# ProPrj_acoustic_imager_2026-03-04.net
KiCad netlist of a schematic drawn in EasyEDA Pro
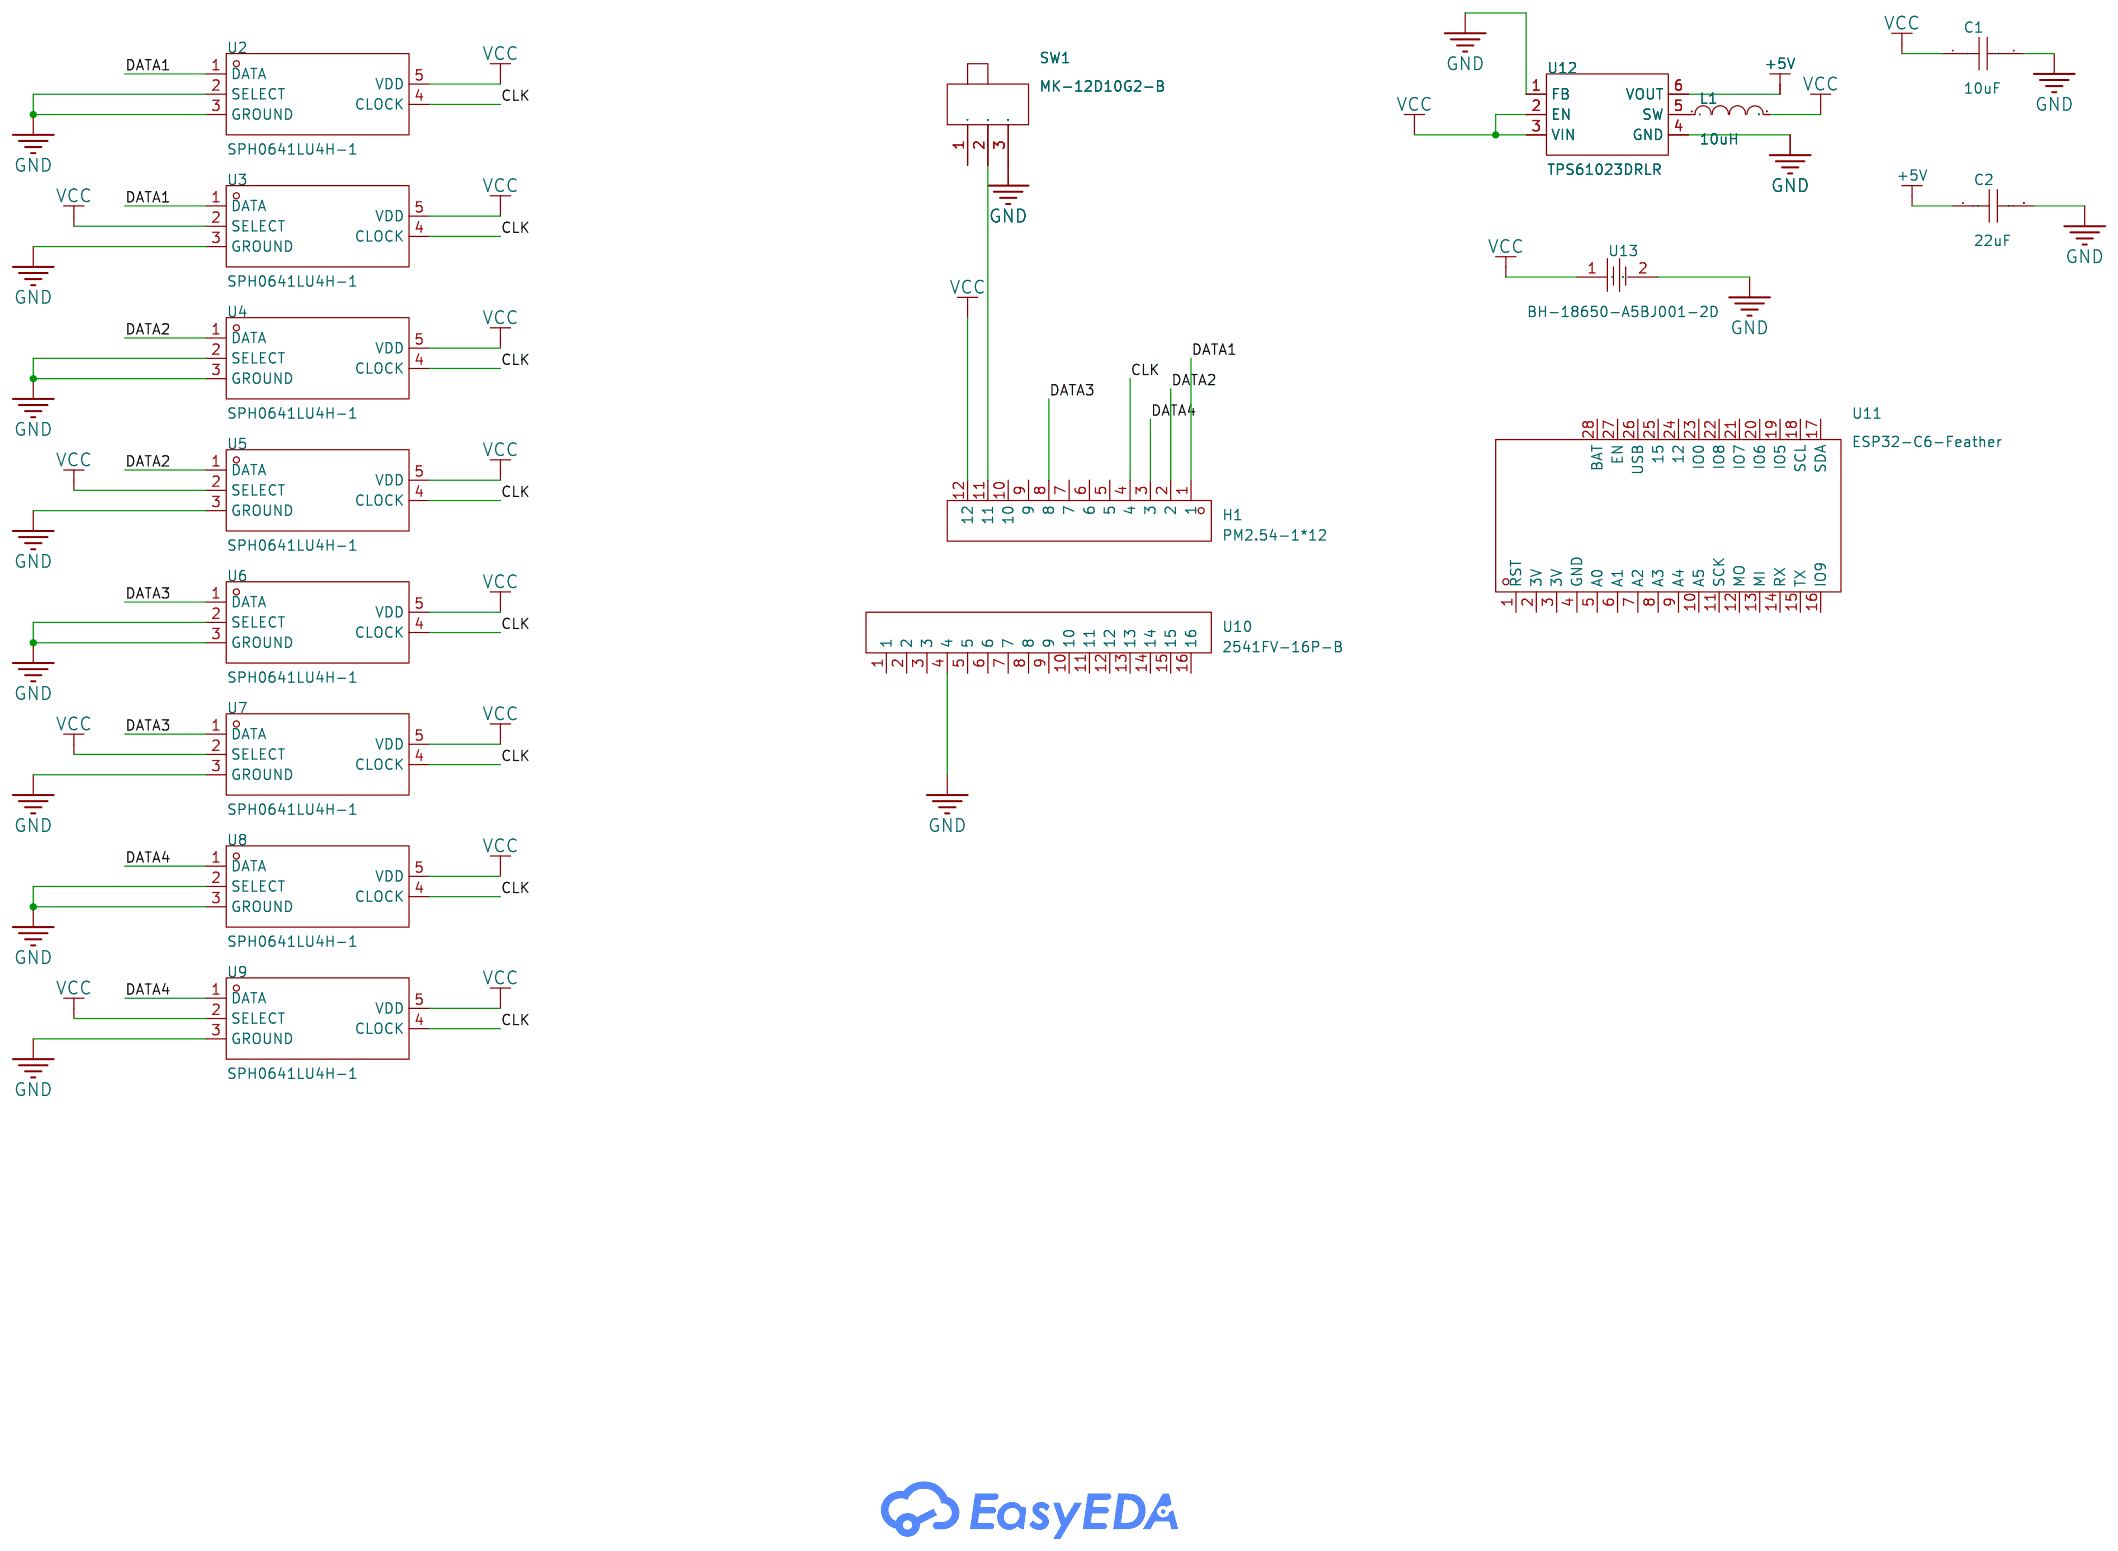
[diagram p0: schematic sheet]

(export (version "E")
  (design (tool "Eeschema 10.0.6"))
  (components
    (comp (ref "C1")
      (value "10uF")
      (footprint "easyedapro:C0805")
      (description "Capacitance:10uF Tolerance:±10% Tolerance:±10% Voltage Rating:50V Temperature Coefficient:X5R")
      (fields
        (field (name "Manufacturer Part") "GRM21BR61H106KE43L")
        (field (name "Manufacturer") "muRata(村田)")
      )
      (libsource (lib "easyedapro") (part "GRM21BR61H106KE43L"))
    )
    (comp (ref "C2")
      (value "22uF")
      (footprint "easyedapro:C0805")
      (description "Capacitance:22uF Tolerance:±20% Tolerance:±20% Voltage Rating:10V Temperature Coefficient:X7R")
      (fields
        (field (name "Manufacturer Part") "GRM21BZ71A226ME15K")
        (field (name "Manufacturer") "muRata(村田)")
      )
      (libsource (lib "easyedapro") (part "GRM21BZ71A226ME15K"))
    )
    (comp (ref "H1")
      (value "PM2.54-1*12")
      (footprint "easyedapro:HDR-TH_12P-P2.54-V-F")
      (fields (field (name "Manufacturer") "ZHOURI(洲日)"))
      (libsource (lib "easyedapro") (part "PM2.54-1*12"))
    )
    (comp (ref "L1")
      (value "10uH")
      (footprint "easyedapro:L0805")
      (fields
        (field (name "Manufacturer Part") "SDFL2012S100KTF")
        (field (name "Manufacturer") "Sunlord(顺络)")
      )
      (libsource (lib "easyedapro") (part "SDFL2012S100KTF"))
    )
    (comp (ref "SW1")
      (value "MK-12D10G2-B")
      (footprint "easyedapro:SW-TH_MK-12D10G2-B")
      (fields (field (name "Manufacturer") "HOOYA(皓宇电子)"))
      (libsource (lib "easyedapro") (part "MK-12D10G2-B"))
    )
    (comp (ref "U2")
      (value "SPH0641LU4H-1")
      (footprint "easyedapro:MIC-SMD_5P_L3.5-W2.7-P0.82_SPH0641LU4H-1")
      (fields (field (name "Manufacturer") "Knowles(楼氏)"))
      (libsource (lib "easyedapro") (part "SPH0641LU4H-1"))
    )
    (comp (ref "U3")
      (value "SPH0641LU4H-1")
      (footprint "easyedapro:MIC-SMD_5P_L3.5-W2.7-P0.82_SPH0641LU4H-1")
      (fields (field (name "Manufacturer") "Knowles(楼氏)"))
      (libsource (lib "easyedapro") (part "SPH0641LU4H-1"))
    )
    (comp (ref "U4")
      (value "SPH0641LU4H-1")
      (footprint "easyedapro:MIC-SMD_5P_L3.5-W2.7-P0.82_SPH0641LU4H-1")
      (fields (field (name "Manufacturer") "Knowles(楼氏)"))
      (libsource (lib "easyedapro") (part "SPH0641LU4H-1"))
    )
    (comp (ref "U5")
      (value "SPH0641LU4H-1")
      (footprint "easyedapro:MIC-SMD_5P_L3.5-W2.7-P0.82_SPH0641LU4H-1")
      (fields (field (name "Manufacturer") "Knowles(楼氏)"))
      (libsource (lib "easyedapro") (part "SPH0641LU4H-1"))
    )
    (comp (ref "U6")
      (value "SPH0641LU4H-1")
      (footprint "easyedapro:MIC-SMD_5P_L3.5-W2.7-P0.82_SPH0641LU4H-1")
      (fields (field (name "Manufacturer") "Knowles(楼氏)"))
      (libsource (lib "easyedapro") (part "SPH0641LU4H-1"))
    )
    (comp (ref "U7")
      (value "SPH0641LU4H-1")
      (footprint "easyedapro:MIC-SMD_5P_L3.5-W2.7-P0.82_SPH0641LU4H-1")
      (fields (field (name "Manufacturer") "Knowles(楼氏)"))
      (libsource (lib "easyedapro") (part "SPH0641LU4H-1"))
    )
    (comp (ref "U8")
      (value "SPH0641LU4H-1")
      (footprint "easyedapro:MIC-SMD_5P_L3.5-W2.7-P0.82_SPH0641LU4H-1")
      (fields (field (name "Manufacturer") "Knowles(楼氏)"))
      (libsource (lib "easyedapro") (part "SPH0641LU4H-1"))
    )
    (comp (ref "U9")
      (value "SPH0641LU4H-1")
      (footprint "easyedapro:MIC-SMD_5P_L3.5-W2.7-P0.82_SPH0641LU4H-1")
      (fields (field (name "Manufacturer") "Knowles(楼氏)"))
      (libsource (lib "easyedapro") (part "SPH0641LU4H-1"))
    )
    (comp (ref "U10")
      (value "2541FV-16P-B")
      (footprint "easyedapro:HDR-TH_16P-P2.54-V-F-4")
      (fields (field (name "Manufacturer") "HanElectricity(瀚源)"))
      (libsource (lib "easyedapro") (part "2541FV-16P-B"))
    )
    (comp (ref "U11")
      (value "ESP32-C6-Feather")
      (footprint "easyedapro:COMM-TH_L50.8-W22.9-P2.54-LS20.32")
      (libsource (lib "easyedapro") (part "ESP32-C6-FEATHER"))
    )
    (comp (ref "U12")
      (value "TPS61023DRLR")
      (footprint "easyedapro:SOT-563_L1.6-W1.2-P0.50-LS1.6-BR")
      (fields (field (name "Manufacturer") "TI(德州仪器)"))
      (libsource (lib "easyedapro") (part "TPS61023DRLR"))
    )
    (comp (ref "U13")
      (value "BH-18650-A5BJ001-2D")
      (footprint "easyedapro:BAT-TH_BH-18650-A5BJ001-2D")
      (description "Type:Battery holder Operating Temperature:-10~100°C Contact coating:Nickel plated")
      (fields (field (name "Manufacturer") "MYOUNG(美阳)"))
      (libsource (lib "easyedapro") (part "BH-18650-A5BJ001-2D"))
    )
  )
  (nets
    (net (code "1") (name "+5V") (class "Default")
      (node (ref "C2") (pin "1") (pinfunction "1_1") (pintype "unspecified"))
      (node (ref "U12") (pin "6") (pinfunction "VOUT_6") (pintype "unspecified"))
    )
    (net (code "2") (name "/CLK") (class "Default")
      (node (ref "H1") (pin "4") (pinfunction "4_4") (pintype "unspecified"))
      (node (ref "U2") (pin "4") (pinfunction "CLOCK_4") (pintype "unspecified"))
      (node (ref "U3") (pin "4") (pinfunction "CLOCK_4") (pintype "unspecified"))
      (node (ref "U4") (pin "4") (pinfunction "CLOCK_4") (pintype "unspecified"))
      (node (ref "U5") (pin "4") (pinfunction "CLOCK_4") (pintype "unspecified"))
      (node (ref "U6") (pin "4") (pinfunction "CLOCK_4") (pintype "unspecified"))
      (node (ref "U7") (pin "4") (pinfunction "CLOCK_4") (pintype "unspecified"))
      (node (ref "U8") (pin "4") (pinfunction "CLOCK_4") (pintype "unspecified"))
      (node (ref "U9") (pin "4") (pinfunction "CLOCK_4") (pintype "unspecified"))
    )
    (net (code "3") (name "/DATA1") (class "Default")
      (node (ref "H1") (pin "1") (pinfunction "1_1") (pintype "unspecified"))
      (node (ref "U2") (pin "1") (pinfunction "DATA_1") (pintype "unspecified"))
      (node (ref "U3") (pin "1") (pinfunction "DATA_1") (pintype "unspecified"))
    )
    (net (code "4") (name "/DATA2") (class "Default")
      (node (ref "H1") (pin "2") (pinfunction "2_2") (pintype "unspecified"))
      (node (ref "U4") (pin "1") (pinfunction "DATA_1") (pintype "unspecified"))
      (node (ref "U5") (pin "1") (pinfunction "DATA_1") (pintype "unspecified"))
    )
    (net (code "5") (name "/DATA3") (class "Default")
      (node (ref "H1") (pin "8") (pinfunction "8_8") (pintype "unspecified"))
      (node (ref "U6") (pin "1") (pinfunction "DATA_1") (pintype "unspecified"))
      (node (ref "U7") (pin "1") (pinfunction "DATA_1") (pintype "unspecified"))
    )
    (net (code "6") (name "/DATA4") (class "Default")
      (node (ref "H1") (pin "3") (pinfunction "3_3") (pintype "unspecified"))
      (node (ref "U8") (pin "1") (pinfunction "DATA_1") (pintype "unspecified"))
      (node (ref "U9") (pin "1") (pinfunction "DATA_1") (pintype "unspecified"))
    )
    (net (code "7") (name "GND") (class "Default")
      (node (ref "C1") (pin "2") (pinfunction "2_2") (pintype "unspecified"))
      (node (ref "C2") (pin "2") (pinfunction "2_2") (pintype "unspecified"))
      (node (ref "SW1") (pin "3") (pinfunction "3_3") (pintype "unspecified"))
      (node (ref "U10") (pin "4") (pinfunction "4_4") (pintype "unspecified"))
      (node (ref "U12") (pin "1") (pinfunction "FB_1") (pintype "unspecified"))
      (node (ref "U12") (pin "4") (pinfunction "GND_4") (pintype "unspecified"))
      (node (ref "U13") (pin "2") (pinfunction "2_2") (pintype "input"))
      (node (ref "U2") (pin "2") (pinfunction "SELECT_2") (pintype "unspecified"))
      (node (ref "U2") (pin "3") (pinfunction "GROUND_3") (pintype "unspecified"))
      (node (ref "U3") (pin "3") (pinfunction "GROUND_3") (pintype "unspecified"))
      (node (ref "U4") (pin "2") (pinfunction "SELECT_2") (pintype "unspecified"))
      (node (ref "U4") (pin "3") (pinfunction "GROUND_3") (pintype "unspecified"))
      (node (ref "U5") (pin "3") (pinfunction "GROUND_3") (pintype "unspecified"))
      (node (ref "U6") (pin "2") (pinfunction "SELECT_2") (pintype "unspecified"))
      (node (ref "U6") (pin "3") (pinfunction "GROUND_3") (pintype "unspecified"))
      (node (ref "U7") (pin "3") (pinfunction "GROUND_3") (pintype "unspecified"))
      (node (ref "U8") (pin "2") (pinfunction "SELECT_2") (pintype "unspecified"))
      (node (ref "U8") (pin "3") (pinfunction "GROUND_3") (pintype "unspecified"))
      (node (ref "U9") (pin "3") (pinfunction "GROUND_3") (pintype "unspecified"))
    )
    (net (code "8") (name "Net-(H1-Pad11)") (class "Default")
      (node (ref "H1") (pin "11") (pinfunction "11_11") (pintype "unspecified"))
      (node (ref "SW1") (pin "2") (pinfunction "2_2") (pintype "unspecified"))
    )
    (net (code "9") (name "Net-(U12-SW)") (class "Default")
      (node (ref "L1") (pin "1") (pinfunction "1_1") (pintype "unspecified"))
      (node (ref "U12") (pin "5") (pinfunction "SW_5") (pintype "unspecified"))
    )
    (net (code "10") (name "VCC") (class "Default")
      (node (ref "C1") (pin "1") (pinfunction "1_1") (pintype "unspecified"))
      (node (ref "H1") (pin "12") (pinfunction "12_12") (pintype "unspecified"))
      (node (ref "L1") (pin "2") (pinfunction "2_2") (pintype "unspecified"))
      (node (ref "U12") (pin "2") (pinfunction "EN_2") (pintype "unspecified"))
      (node (ref "U12") (pin "3") (pinfunction "VIN_3") (pintype "unspecified"))
      (node (ref "U13") (pin "1") (pinfunction "1_1") (pintype "input"))
      (node (ref "U2") (pin "5") (pinfunction "VDD_5") (pintype "unspecified"))
      (node (ref "U3") (pin "2") (pinfunction "SELECT_2") (pintype "unspecified"))
      (node (ref "U3") (pin "5") (pinfunction "VDD_5") (pintype "unspecified"))
      (node (ref "U4") (pin "5") (pinfunction "VDD_5") (pintype "unspecified"))
      (node (ref "U5") (pin "2") (pinfunction "SELECT_2") (pintype "unspecified"))
      (node (ref "U5") (pin "5") (pinfunction "VDD_5") (pintype "unspecified"))
      (node (ref "U6") (pin "5") (pinfunction "VDD_5") (pintype "unspecified"))
      (node (ref "U7") (pin "2") (pinfunction "SELECT_2") (pintype "unspecified"))
      (node (ref "U7") (pin "5") (pinfunction "VDD_5") (pintype "unspecified"))
      (node (ref "U8") (pin "5") (pinfunction "VDD_5") (pintype "unspecified"))
      (node (ref "U9") (pin "2") (pinfunction "SELECT_2") (pintype "unspecified"))
      (node (ref "U9") (pin "5") (pinfunction "VDD_5") (pintype "unspecified"))
    )
    (net (code "11") (name "unconnected-(H1-Pad5)") (class "Default")
      (node (ref "H1") (pin "5") (pinfunction "5_5") (pintype "unspecified"))
    )
    (net (code "12") (name "unconnected-(H1-Pad6)") (class "Default")
      (node (ref "H1") (pin "6") (pinfunction "6_6") (pintype "unspecified"))
    )
    (net (code "13") (name "unconnected-(H1-Pad7)") (class "Default")
      (node (ref "H1") (pin "7") (pinfunction "7_7") (pintype "unspecified"))
    )
    (net (code "14") (name "unconnected-(H1-Pad9)") (class "Default")
      (node (ref "H1") (pin "9") (pinfunction "9_9") (pintype "unspecified"))
    )
    (net (code "15") (name "unconnected-(H1-Pad10)") (class "Default")
      (node (ref "H1") (pin "10") (pinfunction "10_10") (pintype "unspecified"))
    )
    (net (code "16") (name "unconnected-(SW1-Pad1)") (class "Default")
      (node (ref "SW1") (pin "1") (pinfunction "1_1") (pintype "unspecified"))
    )
    (net (code "17") (name "unconnected-(U10-Pad1)") (class "Default")
      (node (ref "U10") (pin "1") (pinfunction "1_1") (pintype "unspecified"))
    )
    (net (code "18") (name "unconnected-(U10-Pad2)") (class "Default")
      (node (ref "U10") (pin "2") (pinfunction "2_2") (pintype "unspecified"))
    )
    (net (code "19") (name "unconnected-(U10-Pad3)") (class "Default")
      (node (ref "U10") (pin "3") (pinfunction "3_3") (pintype "unspecified"))
    )
    (net (code "20") (name "unconnected-(U10-Pad5)") (class "Default")
      (node (ref "U10") (pin "5") (pinfunction "5_5") (pintype "unspecified"))
    )
    (net (code "21") (name "unconnected-(U10-Pad6)") (class "Default")
      (node (ref "U10") (pin "6") (pinfunction "6_6") (pintype "unspecified"))
    )
    (net (code "22") (name "unconnected-(U10-Pad7)") (class "Default")
      (node (ref "U10") (pin "7") (pinfunction "7_7") (pintype "unspecified"))
    )
    (net (code "23") (name "unconnected-(U10-Pad8)") (class "Default")
      (node (ref "U10") (pin "8") (pinfunction "8_8") (pintype "unspecified"))
    )
    (net (code "24") (name "unconnected-(U10-Pad9)") (class "Default")
      (node (ref "U10") (pin "9") (pinfunction "9_9") (pintype "unspecified"))
    )
    (net (code "25") (name "unconnected-(U10-Pad10)") (class "Default")
      (node (ref "U10") (pin "10") (pinfunction "10_10") (pintype "unspecified"))
    )
    (net (code "26") (name "unconnected-(U10-Pad11)") (class "Default")
      (node (ref "U10") (pin "11") (pinfunction "11_11") (pintype "unspecified"))
    )
    (net (code "27") (name "unconnected-(U10-Pad12)") (class "Default")
      (node (ref "U10") (pin "12") (pinfunction "12_12") (pintype "unspecified"))
    )
    (net (code "28") (name "unconnected-(U10-Pad13)") (class "Default")
      (node (ref "U10") (pin "13") (pinfunction "13_13") (pintype "unspecified"))
    )
    (net (code "29") (name "unconnected-(U10-Pad14)") (class "Default")
      (node (ref "U10") (pin "14") (pinfunction "14_14") (pintype "unspecified"))
    )
    (net (code "30") (name "unconnected-(U10-Pad15)") (class "Default")
      (node (ref "U10") (pin "15") (pinfunction "15_15") (pintype "unspecified"))
    )
    (net (code "31") (name "unconnected-(U10-Pad16)") (class "Default")
      (node (ref "U10") (pin "16") (pinfunction "16_16") (pintype "unspecified"))
    )
    (net (code "32") (name "unconnected-(U11-3V-Pad2)") (class "Default")
      (node (ref "U11") (pin "2") (pinfunction "3V_2") (pintype "unspecified"))
    )
    (net (code "33") (name "unconnected-(U11-3V-Pad3)") (class "Default")
      (node (ref "U11") (pin "3") (pinfunction "3V_3") (pintype "unspecified"))
    )
    (net (code "34") (name "unconnected-(U11-12-Pad24)") (class "Default")
      (node (ref "U11") (pin "24") (pinfunction "12_24") (pintype "unspecified"))
    )
    (net (code "35") (name "unconnected-(U11-15-Pad25)") (class "Default")
      (node (ref "U11") (pin "25") (pinfunction "15_25") (pintype "unspecified"))
    )
    (net (code "36") (name "unconnected-(U11-A0-Pad5)") (class "Default")
      (node (ref "U11") (pin "5") (pinfunction "A0_5") (pintype "unspecified"))
    )
    (net (code "37") (name "unconnected-(U11-A1-Pad6)") (class "Default")
      (node (ref "U11") (pin "6") (pinfunction "A1_6") (pintype "unspecified"))
    )
    (net (code "38") (name "unconnected-(U11-A2-Pad7)") (class "Default")
      (node (ref "U11") (pin "7") (pinfunction "A2_7") (pintype "unspecified"))
    )
    (net (code "39") (name "unconnected-(U11-A3-Pad8)") (class "Default")
      (node (ref "U11") (pin "8") (pinfunction "A3_8") (pintype "unspecified"))
    )
    (net (code "40") (name "unconnected-(U11-A4-Pad9)") (class "Default")
      (node (ref "U11") (pin "9") (pinfunction "A4_9") (pintype "unspecified"))
    )
    (net (code "41") (name "unconnected-(U11-A5-Pad10)") (class "Default")
      (node (ref "U11") (pin "10") (pinfunction "A5_10") (pintype "unspecified"))
    )
    (net (code "42") (name "unconnected-(U11-BAT-Pad28)") (class "Default")
      (node (ref "U11") (pin "28") (pinfunction "BAT_28") (pintype "unspecified"))
    )
    (net (code "43") (name "unconnected-(U11-EN-Pad27)") (class "Default")
      (node (ref "U11") (pin "27") (pinfunction "EN_27") (pintype "unspecified"))
    )
    (net (code "44") (name "unconnected-(U11-GND-Pad4)") (class "Default")
      (node (ref "U11") (pin "4") (pinfunction "GND_4") (pintype "unspecified"))
    )
    (net (code "45") (name "unconnected-(U11-IO0-Pad23)") (class "Default")
      (node (ref "U11") (pin "23") (pinfunction "IO0_23") (pintype "unspecified"))
    )
    (net (code "46") (name "unconnected-(U11-IO5-Pad19)") (class "Default")
      (node (ref "U11") (pin "19") (pinfunction "IO5_19") (pintype "unspecified"))
    )
    (net (code "47") (name "unconnected-(U11-IO6-Pad20)") (class "Default")
      (node (ref "U11") (pin "20") (pinfunction "IO6_20") (pintype "unspecified"))
    )
    (net (code "48") (name "unconnected-(U11-IO7-Pad21)") (class "Default")
      (node (ref "U11") (pin "21") (pinfunction "IO7_21") (pintype "unspecified"))
    )
    (net (code "49") (name "unconnected-(U11-IO8-Pad22)") (class "Default")
      (node (ref "U11") (pin "22") (pinfunction "IO8_22") (pintype "unspecified"))
    )
    (net (code "50") (name "unconnected-(U11-IO9-Pad16)") (class "Default")
      (node (ref "U11") (pin "16") (pinfunction "IO9_16") (pintype "unspecified"))
    )
    (net (code "51") (name "unconnected-(U11-MI-Pad13)") (class "Default")
      (node (ref "U11") (pin "13") (pinfunction "MI_13") (pintype "unspecified"))
    )
    (net (code "52") (name "unconnected-(U11-MO-Pad12)") (class "Default")
      (node (ref "U11") (pin "12") (pinfunction "MO_12") (pintype "unspecified"))
    )
    (net (code "53") (name "unconnected-(U11-RST-Pad1)") (class "Default")
      (node (ref "U11") (pin "1") (pinfunction "RST_1") (pintype "unspecified"))
    )
    (net (code "54") (name "unconnected-(U11-RX-Pad14)") (class "Default")
      (node (ref "U11") (pin "14") (pinfunction "RX_14") (pintype "unspecified"))
    )
    (net (code "55") (name "unconnected-(U11-SCK-Pad11)") (class "Default")
      (node (ref "U11") (pin "11") (pinfunction "SCK_11") (pintype "unspecified"))
    )
    (net (code "56") (name "unconnected-(U11-SCL-Pad18)") (class "Default")
      (node (ref "U11") (pin "18") (pinfunction "SCL_18") (pintype "unspecified"))
    )
    (net (code "57") (name "unconnected-(U11-SDA-Pad17)") (class "Default")
      (node (ref "U11") (pin "17") (pinfunction "SDA_17") (pintype "unspecified"))
    )
    (net (code "58") (name "unconnected-(U11-TX-Pad15)") (class "Default")
      (node (ref "U11") (pin "15") (pinfunction "TX_15") (pintype "unspecified"))
    )
    (net (code "59") (name "unconnected-(U11-USB-Pad26)") (class "Default")
      (node (ref "U11") (pin "26") (pinfunction "USB_26") (pintype "unspecified"))
    )
  )
)
